# v1.net
KiCad netlist of a schematic drawn in EAGLE
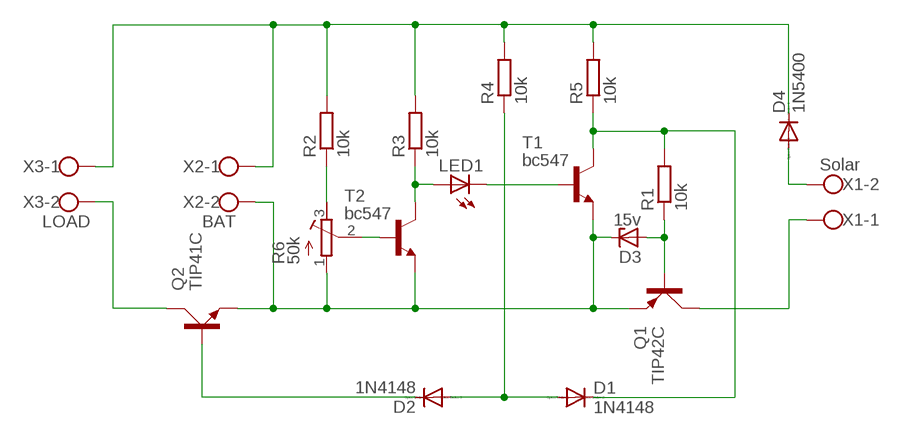
[diagram p0: schematic, sheet 1]

(export (version "E")
  (design (tool "Eeschema 10.0.6"))
  (components
    (comp (ref "D1")
      (value "1N4148")
      (footprint "eagle-import:DO35-10")
      (libsource (lib "eagle-import") (part "1N4148DO35-10"))
    )
    (comp (ref "D2")
      (value "1N4148")
      (footprint "eagle-import:DO35-10")
      (libsource (lib "eagle-import") (part "1N4148DO35-10"))
    )
    (comp (ref "D3")
      (value "15v")
      (footprint "eagle-import:ZDIO-10")
      (libsource (lib "eagle-import") (part "ZENER-DIODEZD-10"))
    )
    (comp (ref "D4")
      (value "1N5400")
      (footprint "eagle-import:DO201-15")
      (libsource (lib "eagle-import") (part "1N5400"))
    )
    (comp (ref "LED1")
      (value "LED5MM")
      (footprint "eagle-import:LED5MM")
      (libsource (lib "eagle-import") (part "LED5MM"))
    )
    (comp (ref "Q1")
      (value "TIP42C")
      (footprint "eagle-import:TO220AV")
      (libsource (lib "eagle-import") (part "TIP42C"))
    )
    (comp (ref "Q2")
      (value "TIP41C")
      (footprint "eagle-import:TO220AV")
      (libsource (lib "eagle-import") (part "TIP41C"))
    )
    (comp (ref "R1")
      (value "10k")
      (footprint "eagle-import:0207_10")
      (libsource (lib "eagle-import") (part "R-EU_0207/10"))
    )
    (comp (ref "R2")
      (value "10k")
      (footprint "eagle-import:0207_10")
      (libsource (lib "eagle-import") (part "R-EU_0207/10"))
    )
    (comp (ref "R3")
      (value "10k")
      (footprint "eagle-import:0207_10")
      (libsource (lib "eagle-import") (part "R-EU_0207/10"))
    )
    (comp (ref "R4")
      (value "10k")
      (footprint "eagle-import:0207_10")
      (libsource (lib "eagle-import") (part "R-EU_0207/10"))
    )
    (comp (ref "R5")
      (value "10k")
      (footprint "eagle-import:0207_10")
      (libsource (lib "eagle-import") (part "R-EU_0207/10"))
    )
    (comp (ref "R6")
      (value "50k")
      (footprint "eagle-import:RTRIM64W")
      (libsource (lib "eagle-import") (part "R-TRIMM64W"))
    )
    (comp (ref "T1")
      (value "bc547")
      (footprint "eagle-import:TO92-CBE")
      (libsource (lib "eagle-import") (part "-NPN-TO92-CBEBC547"))
    )
    (comp (ref "T2")
      (value "bc547")
      (footprint "eagle-import:TO92-CBE")
      (libsource (lib "eagle-import") (part "-NPN-TO92-CBEBC547"))
    )
    (comp (ref "X1")
      (value "Solar")
      (footprint "eagle-import:W237-102")
      (fields (field (name "MPN") "237-102"))
      (libsource (lib "eagle-import") (part "W237-102"))
    )
    (comp (ref "X2")
      (value "BAT")
      (footprint "eagle-import:W237-102")
      (fields (field (name "MPN") "237-102"))
      (libsource (lib "eagle-import") (part "W237-102"))
    )
    (comp (ref "X3")
      (value "LOAD")
      (footprint "eagle-import:W237-102")
      (fields (field (name "MPN") "237-102"))
      (libsource (lib "eagle-import") (part "W237-102"))
    )
  )
  (nets
    (net (code "1") (name "Net-(D1-PadA)") (class "Default")
      (node (ref "D1") (pin "A") (pinfunction "A_A") (pintype "passive"))
      (node (ref "D2") (pin "A") (pinfunction "A_A") (pintype "passive"))
      (node (ref "R4") (pin "1") (pinfunction "1_1") (pintype "passive"))
    )
    (net (code "2") (name "Net-(D1-PadC)") (class "Default")
      (node (ref "D1") (pin "C") (pinfunction "C_C") (pintype "passive"))
      (node (ref "R1") (pin "2") (pinfunction "2_2") (pintype "passive"))
      (node (ref "R5") (pin "1") (pinfunction "1_1") (pintype "passive"))
      (node (ref "T1") (pin "C") (pinfunction "C_C") (pintype "passive"))
    )
    (net (code "3") (name "Net-(D2-PadC)") (class "Default")
      (node (ref "D2") (pin "C") (pinfunction "C_C") (pintype "passive"))
      (node (ref "Q2") (pin "B") (pinfunction "B_B") (pintype "passive"))
    )
    (net (code "4") (name "Net-(D3-PadA)") (class "Default")
      (node (ref "D3") (pin "A") (pinfunction "A_A") (pintype "passive"))
      (node (ref "Q1") (pin "B") (pinfunction "B_B") (pintype "passive"))
      (node (ref "R1") (pin "1") (pinfunction "1_1") (pintype "passive"))
    )
    (net (code "5") (name "Net-(LED1-C)") (class "Default")
      (node (ref "LED1") (pin "K") (pinfunction "C_K") (pintype "passive"))
      (node (ref "T1") (pin "B") (pinfunction "B_B") (pintype "passive"))
    )
    (net (code "6") (name "Net-(LED1-PadA)") (class "Default")
      (node (ref "LED1") (pin "A") (pinfunction "A_A") (pintype "passive"))
      (node (ref "R3") (pin "1") (pinfunction "1_1") (pintype "passive"))
      (node (ref "T2") (pin "C") (pinfunction "C_C") (pintype "passive"))
    )
    (net (code "7") (name "Net-(R6-A)") (class "Default")
      (node (ref "D3") (pin "C") (pinfunction "C_C") (pintype "passive"))
      (node (ref "Q1") (pin "E") (pinfunction "E_E") (pintype "passive"))
      (node (ref "Q2") (pin "E") (pinfunction "E_E") (pintype "passive"))
      (node (ref "R6") (pin "1") (pinfunction "A_1") (pintype "passive"))
      (node (ref "T1") (pin "E") (pinfunction "E_E") (pintype "passive"))
      (node (ref "T2") (pin "E") (pinfunction "E_E") (pintype "passive"))
      (node (ref "X2") (pin "2") (pinfunction "KL_2") (pintype "passive"))
    )
    (net (code "8") (name "Net-(R6-E)") (class "Default")
      (node (ref "R2") (pin "1") (pinfunction "1_1") (pintype "passive"))
      (node (ref "R6") (pin "3") (pinfunction "E_3") (pintype "passive"))
    )
    (net (code "9") (name "Net-(R6-S)") (class "Default")
      (node (ref "R6") (pin "2") (pinfunction "S_2") (pintype "passive"))
      (node (ref "T2") (pin "B") (pinfunction "B_B") (pintype "passive"))
    )
    (net (code "10") (name "Net-(X1A-KL)") (class "Default")
      (node (ref "Q1") (pin "C") (pinfunction "C_C") (pintype "passive"))
      (node (ref "X1") (pin "1") (pinfunction "KL_1") (pintype "passive"))
    )
    (net (code "11") (name "Net-(X1B-KL)") (class "Default")
      (node (ref "D4") (pin "A") (pinfunction "A_A") (pintype "passive"))
      (node (ref "X1") (pin "2") (pinfunction "KL_2") (pintype "passive"))
    )
    (net (code "12") (name "Net-(X2A-KL)") (class "Default")
      (node (ref "D4") (pin "C") (pinfunction "C_C") (pintype "passive"))
      (node (ref "R2") (pin "2") (pinfunction "2_2") (pintype "passive"))
      (node (ref "R3") (pin "2") (pinfunction "2_2") (pintype "passive"))
      (node (ref "R4") (pin "2") (pinfunction "2_2") (pintype "passive"))
      (node (ref "R5") (pin "2") (pinfunction "2_2") (pintype "passive"))
      (node (ref "X2") (pin "1") (pinfunction "KL_1") (pintype "passive"))
      (node (ref "X3") (pin "1") (pinfunction "KL_1") (pintype "passive"))
    )
    (net (code "13") (name "Net-(X3B-KL)") (class "Default")
      (node (ref "Q2") (pin "C") (pinfunction "C_C") (pintype "passive"))
      (node (ref "X3") (pin "2") (pinfunction "KL_2") (pintype "passive"))
    )
  )
)
